# PCB_schematic_v1_0.net
KiCad netlist of a schematic drawn in EAGLE
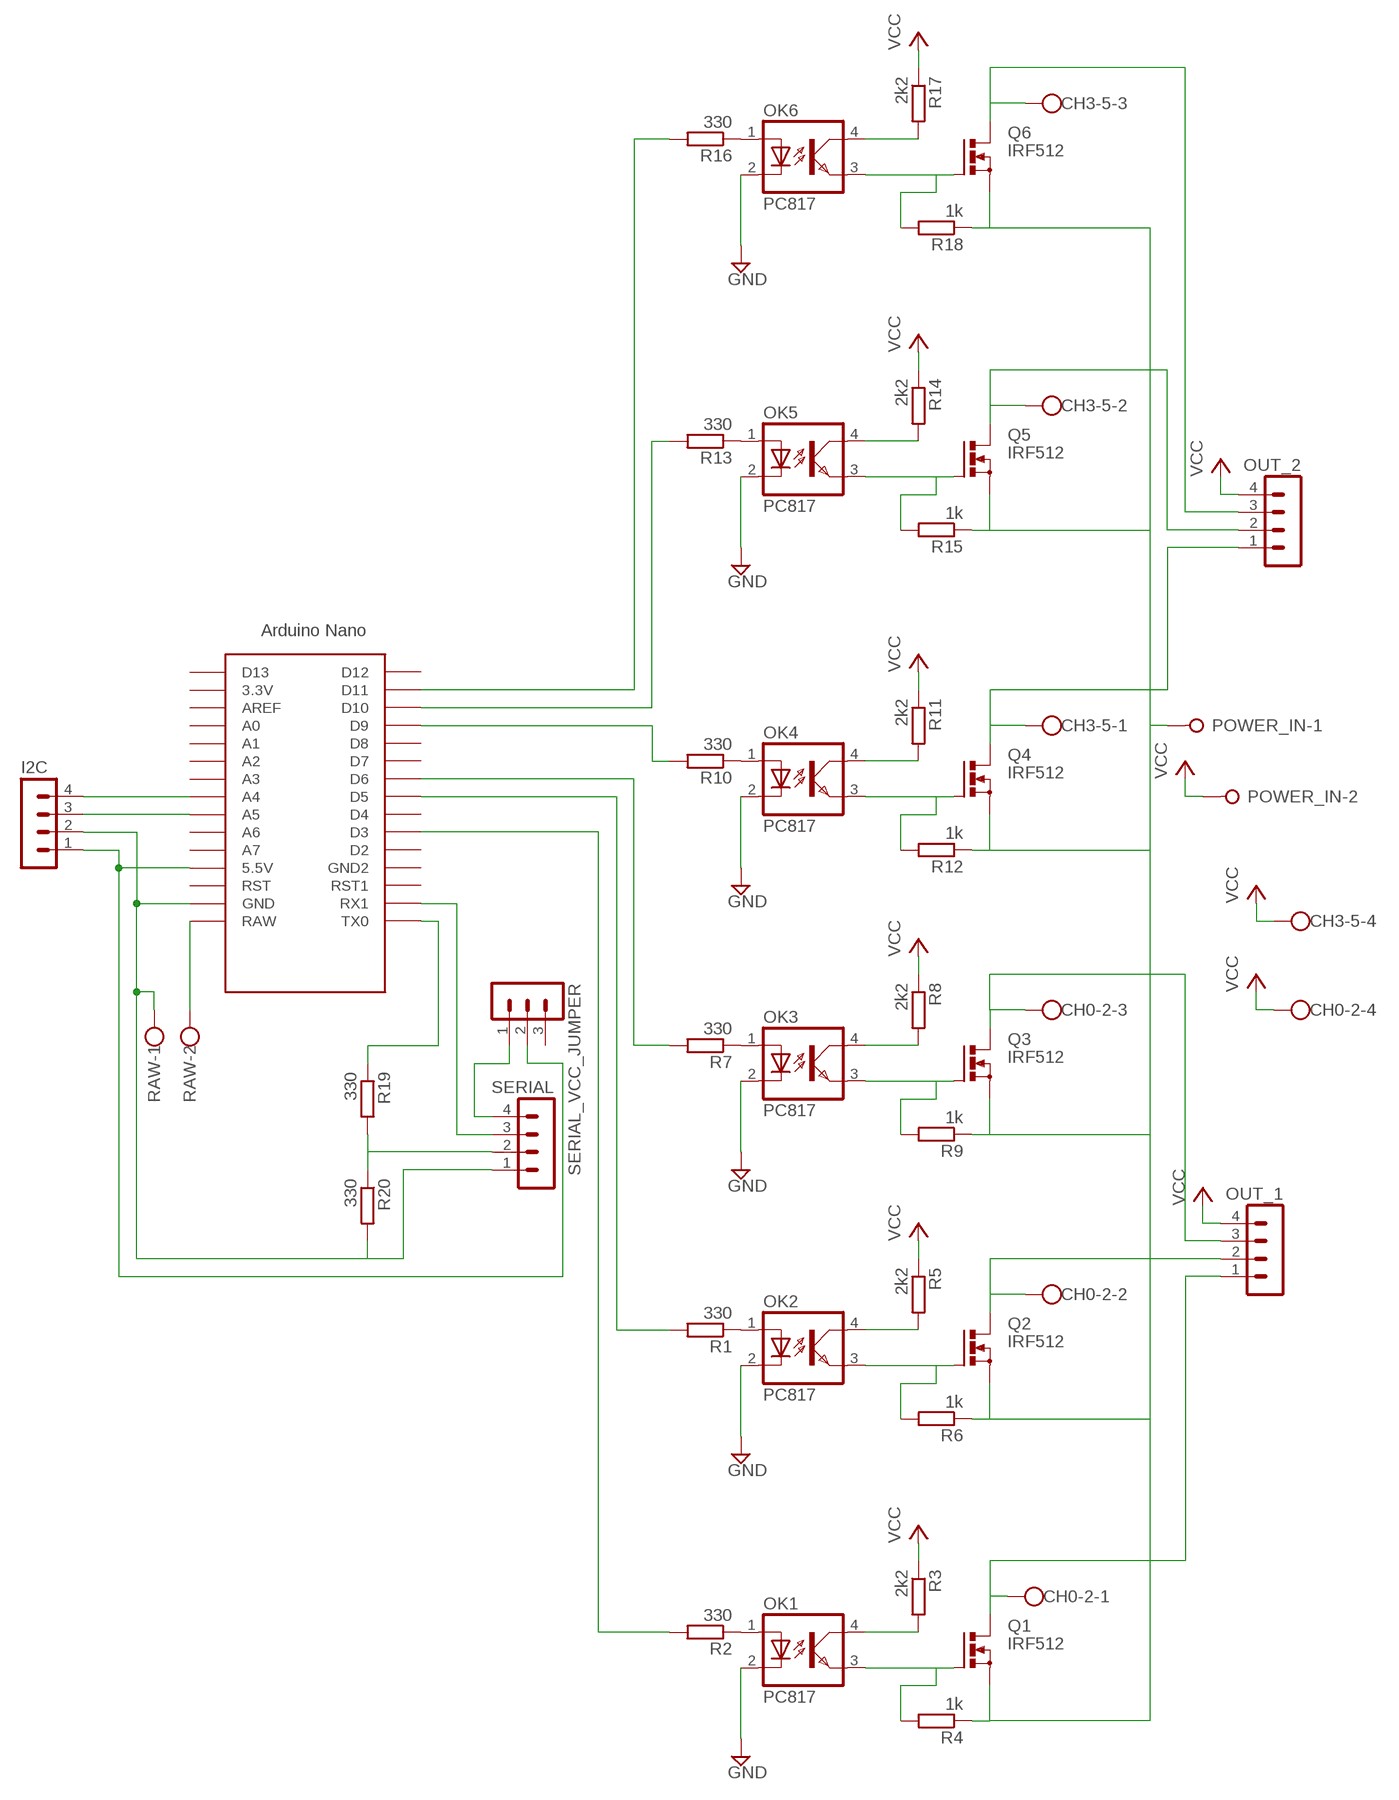
[diagram p0: schematic, sheet 1]

(export (version "E")
  (design (tool "Eeschema 10.0.6"))
  (components
    (comp (ref "CH0-2")
      (value "W237-4")
      (footprint "eagle-import:W237-4")
      (libsource (lib "eagle-import") (part "W237-4"))
    )
    (comp (ref "CH3-5")
      (value "W237-4")
      (footprint "eagle-import:W237-4")
      (libsource (lib "eagle-import") (part "W237-4"))
    )
    (comp (ref "I2C")
      (value "MA04-1")
      (footprint "eagle-import:MA04-1")
      (libsource (lib "eagle-import") (part "MA04-1"))
    )
    (comp (ref "OK1")
      (value "PC817")
      (footprint "eagle-import:DIL04")
      (fields (field (name "MPN") "PC817X4J000F"))
      (libsource (lib "eagle-import") (part "PC817"))
    )
    (comp (ref "OK2")
      (value "PC817")
      (footprint "eagle-import:DIL04")
      (fields (field (name "MPN") "PC817X4J000F"))
      (libsource (lib "eagle-import") (part "PC817"))
    )
    (comp (ref "OK3")
      (value "PC817")
      (footprint "eagle-import:DIL04")
      (fields (field (name "MPN") "PC817X4J000F"))
      (libsource (lib "eagle-import") (part "PC817"))
    )
    (comp (ref "OK4")
      (value "PC817")
      (footprint "eagle-import:DIL04")
      (fields (field (name "MPN") "PC817X4J000F"))
      (libsource (lib "eagle-import") (part "PC817"))
    )
    (comp (ref "OK5")
      (value "PC817")
      (footprint "eagle-import:DIL04")
      (fields (field (name "MPN") "PC817X4J000F"))
      (libsource (lib "eagle-import") (part "PC817"))
    )
    (comp (ref "OK6")
      (value "PC817")
      (footprint "eagle-import:DIL04")
      (fields (field (name "MPN") "PC817X4J000F"))
      (libsource (lib "eagle-import") (part "PC817"))
    )
    (comp (ref "OUT_1")
      (value "MA04-1")
      (footprint "eagle-import:MA04-1")
      (libsource (lib "eagle-import") (part "MA04-1"))
    )
    (comp (ref "OUT_2")
      (value "MA04-1")
      (footprint "eagle-import:MA04-1")
      (libsource (lib "eagle-import") (part "MA04-1"))
    )
    (comp (ref "POWER_IN")
      (value "W237-02P")
      (footprint "eagle-import:W237-132")
      (libsource (lib "eagle-import") (part "W237-02P"))
    )
    (comp (ref "Q1")
      (value "IRF512")
      (footprint "eagle-import:TO220BV")
      (libsource (lib "eagle-import") (part "IRF512"))
    )
    (comp (ref "Q2")
      (value "IRF512")
      (footprint "eagle-import:TO220BV")
      (libsource (lib "eagle-import") (part "IRF512"))
    )
    (comp (ref "Q3")
      (value "IRF512")
      (footprint "eagle-import:TO220BV")
      (libsource (lib "eagle-import") (part "IRF512"))
    )
    (comp (ref "Q4")
      (value "IRF512")
      (footprint "eagle-import:TO220BV")
      (libsource (lib "eagle-import") (part "IRF512"))
    )
    (comp (ref "Q5")
      (value "IRF512")
      (footprint "eagle-import:TO220BV")
      (libsource (lib "eagle-import") (part "IRF512"))
    )
    (comp (ref "Q6")
      (value "IRF512")
      (footprint "eagle-import:TO220BV")
      (libsource (lib "eagle-import") (part "IRF512"))
    )
    (comp (ref "R1")
      (value "330")
      (footprint "eagle-import:0207_10")
      (libsource (lib "eagle-import") (part "R-EU_0207/10"))
    )
    (comp (ref "R2")
      (value "330")
      (footprint "eagle-import:0207_10")
      (libsource (lib "eagle-import") (part "R-EU_0207/10"))
    )
    (comp (ref "R3")
      (value "2k2")
      (footprint "eagle-import:0207_10")
      (libsource (lib "eagle-import") (part "R-EU_0207/10"))
    )
    (comp (ref "R4")
      (value "1k")
      (footprint "eagle-import:0207_10")
      (libsource (lib "eagle-import") (part "R-EU_0207/10"))
    )
    (comp (ref "R5")
      (value "2k2")
      (footprint "eagle-import:0207_10")
      (libsource (lib "eagle-import") (part "R-EU_0207/10"))
    )
    (comp (ref "R6")
      (value "1k")
      (footprint "eagle-import:0207_10")
      (libsource (lib "eagle-import") (part "R-EU_0207/10"))
    )
    (comp (ref "R7")
      (value "330")
      (footprint "eagle-import:0207_10")
      (libsource (lib "eagle-import") (part "R-EU_0207/10"))
    )
    (comp (ref "R8")
      (value "2k2")
      (footprint "eagle-import:0207_10")
      (libsource (lib "eagle-import") (part "R-EU_0207/10"))
    )
    (comp (ref "R9")
      (value "1k")
      (footprint "eagle-import:0207_10")
      (libsource (lib "eagle-import") (part "R-EU_0207/10"))
    )
    (comp (ref "R10")
      (value "330")
      (footprint "eagle-import:0207_10")
      (libsource (lib "eagle-import") (part "R-EU_0207/10"))
    )
    (comp (ref "R11")
      (value "2k2")
      (footprint "eagle-import:0207_10")
      (libsource (lib "eagle-import") (part "R-EU_0207/10"))
    )
    (comp (ref "R12")
      (value "1k")
      (footprint "eagle-import:0207_10")
      (libsource (lib "eagle-import") (part "R-EU_0207/10"))
    )
    (comp (ref "R13")
      (value "330")
      (footprint "eagle-import:0207_10")
      (libsource (lib "eagle-import") (part "R-EU_0207/10"))
    )
    (comp (ref "R14")
      (value "2k2")
      (footprint "eagle-import:0207_10")
      (libsource (lib "eagle-import") (part "R-EU_0207/10"))
    )
    (comp (ref "R15")
      (value "1k")
      (footprint "eagle-import:0207_10")
      (libsource (lib "eagle-import") (part "R-EU_0207/10"))
    )
    (comp (ref "R16")
      (value "330")
      (footprint "eagle-import:0207_10")
      (libsource (lib "eagle-import") (part "R-EU_0207/10"))
    )
    (comp (ref "R17")
      (value "2k2")
      (footprint "eagle-import:0207_10")
      (libsource (lib "eagle-import") (part "R-EU_0207/10"))
    )
    (comp (ref "R18")
      (value "1k")
      (footprint "eagle-import:0207_10")
      (libsource (lib "eagle-import") (part "R-EU_0207/10"))
    )
    (comp (ref "R19")
      (value "330")
      (footprint "eagle-import:0207_10")
      (libsource (lib "eagle-import") (part "R-EU_0207/10"))
    )
    (comp (ref "R20")
      (value "330")
      (footprint "eagle-import:0207_10")
      (libsource (lib "eagle-import") (part "R-EU_0207/10"))
    )
    (comp (ref "RAW")
      (value "W237-102")
      (footprint "eagle-import:W237-102")
      (fields (field (name "MPN") "237-102"))
      (libsource (lib "eagle-import") (part "W237-102"))
    )
    (comp (ref "SERIAL")
      (value "MA04-1")
      (footprint "eagle-import:MA04-1")
      (libsource (lib "eagle-import") (part "MA04-1"))
    )
    (comp (ref "SERIAL_VCC_JUMPER")
      (value "MA03-1")
      (footprint "eagle-import:MA03-1")
      (libsource (lib "eagle-import") (part "MA03-1"))
    )
    (comp (ref "U$1")
      (value "NANO")
      (footprint "eagle-import:NANO")
      (libsource (lib "eagle-import") (part "NANO"))
    )
  )
  (nets
    (net (code "1") (name "GND") (class "Default")
      (node (ref "OK1") (pin "2") (pinfunction "C_2") (pintype "passive"))
      (node (ref "OK2") (pin "2") (pinfunction "C_2") (pintype "passive"))
      (node (ref "OK3") (pin "2") (pinfunction "C_2") (pintype "passive"))
      (node (ref "OK4") (pin "2") (pinfunction "C_2") (pintype "passive"))
      (node (ref "OK5") (pin "2") (pinfunction "C_2") (pintype "passive"))
      (node (ref "OK6") (pin "2") (pinfunction "C_2") (pintype "passive"))
    )
    (net (code "2") (name "Net-(CH0-2A-KL)") (class "Default")
      (node (ref "CH0-2") (pin "1") (pinfunction "KL_1") (pintype "passive"))
      (node (ref "OUT_1") (pin "1") (pinfunction "1_1") (pintype "passive"))
      (node (ref "Q1") (pin "D") (pinfunction "D_D") (pintype "passive"))
    )
    (net (code "3") (name "Net-(CH0-2B-KL)") (class "Default")
      (node (ref "CH0-2") (pin "2") (pinfunction "KL_2") (pintype "passive"))
      (node (ref "OUT_1") (pin "2") (pinfunction "2_2") (pintype "passive"))
      (node (ref "Q2") (pin "D") (pinfunction "D_D") (pintype "passive"))
    )
    (net (code "4") (name "Net-(CH0-2C-KL)") (class "Default")
      (node (ref "CH0-2") (pin "3") (pinfunction "KL_3") (pintype "passive"))
      (node (ref "OUT_1") (pin "3") (pinfunction "3_3") (pintype "passive"))
      (node (ref "Q3") (pin "D") (pinfunction "D_D") (pintype "passive"))
    )
    (net (code "5") (name "Net-(CH3-5A-KL)") (class "Default")
      (node (ref "CH3-5") (pin "1") (pinfunction "KL_1") (pintype "passive"))
      (node (ref "OUT_2") (pin "1") (pinfunction "1_1") (pintype "passive"))
      (node (ref "Q4") (pin "D") (pinfunction "D_D") (pintype "passive"))
    )
    (net (code "6") (name "Net-(CH3-5B-KL)") (class "Default")
      (node (ref "CH3-5") (pin "2") (pinfunction "KL_2") (pintype "passive"))
      (node (ref "OUT_2") (pin "2") (pinfunction "2_2") (pintype "passive"))
      (node (ref "Q5") (pin "D") (pinfunction "D_D") (pintype "passive"))
    )
    (net (code "7") (name "Net-(CH3-5C-KL)") (class "Default")
      (node (ref "CH3-5") (pin "3") (pinfunction "KL_3") (pintype "passive"))
      (node (ref "OUT_2") (pin "3") (pinfunction "3_3") (pintype "passive"))
      (node (ref "Q6") (pin "D") (pinfunction "D_D") (pintype "passive"))
    )
    (net (code "8") (name "Net-(I2C-Pad3)") (class "Default")
      (node (ref "I2C") (pin "3") (pinfunction "3_3") (pintype "passive"))
      (node (ref "U$1") (pin "A5") (pinfunction "A5_A5") (pintype "bidirectional"))
    )
    (net (code "9") (name "Net-(I2C-Pad4)") (class "Default")
      (node (ref "I2C") (pin "4") (pinfunction "4_4") (pintype "passive"))
      (node (ref "U$1") (pin "A4") (pinfunction "A4_A4") (pintype "bidirectional"))
    )
    (net (code "10") (name "Net-(OK1-A)") (class "Default")
      (node (ref "OK1") (pin "1") (pinfunction "A_1") (pintype "passive"))
      (node (ref "R2") (pin "1") (pinfunction "1_1") (pintype "passive"))
    )
    (net (code "11") (name "Net-(OK1-COL)") (class "Default")
      (node (ref "OK1") (pin "4") (pinfunction "COL_4") (pintype "passive"))
      (node (ref "R3") (pin "2") (pinfunction "2_2") (pintype "passive"))
    )
    (net (code "12") (name "Net-(OK1-EMIT)") (class "Default")
      (node (ref "OK1") (pin "3") (pinfunction "EMIT_3") (pintype "passive"))
      (node (ref "Q1") (pin "G") (pinfunction "G_G") (pintype "passive"))
      (node (ref "R4") (pin "2") (pinfunction "2_2") (pintype "passive"))
    )
    (net (code "13") (name "Net-(OK2-A)") (class "Default")
      (node (ref "OK2") (pin "1") (pinfunction "A_1") (pintype "passive"))
      (node (ref "R1") (pin "1") (pinfunction "1_1") (pintype "passive"))
    )
    (net (code "14") (name "Net-(OK2-COL)") (class "Default")
      (node (ref "OK2") (pin "4") (pinfunction "COL_4") (pintype "passive"))
      (node (ref "R5") (pin "2") (pinfunction "2_2") (pintype "passive"))
    )
    (net (code "15") (name "Net-(OK2-EMIT)") (class "Default")
      (node (ref "OK2") (pin "3") (pinfunction "EMIT_3") (pintype "passive"))
      (node (ref "Q2") (pin "G") (pinfunction "G_G") (pintype "passive"))
      (node (ref "R6") (pin "2") (pinfunction "2_2") (pintype "passive"))
    )
    (net (code "16") (name "Net-(OK3-A)") (class "Default")
      (node (ref "OK3") (pin "1") (pinfunction "A_1") (pintype "passive"))
      (node (ref "R7") (pin "1") (pinfunction "1_1") (pintype "passive"))
    )
    (net (code "17") (name "Net-(OK3-COL)") (class "Default")
      (node (ref "OK3") (pin "4") (pinfunction "COL_4") (pintype "passive"))
      (node (ref "R8") (pin "2") (pinfunction "2_2") (pintype "passive"))
    )
    (net (code "18") (name "Net-(OK3-EMIT)") (class "Default")
      (node (ref "OK3") (pin "3") (pinfunction "EMIT_3") (pintype "passive"))
      (node (ref "Q3") (pin "G") (pinfunction "G_G") (pintype "passive"))
      (node (ref "R9") (pin "2") (pinfunction "2_2") (pintype "passive"))
    )
    (net (code "19") (name "Net-(OK4-A)") (class "Default")
      (node (ref "OK4") (pin "1") (pinfunction "A_1") (pintype "passive"))
      (node (ref "R10") (pin "1") (pinfunction "1_1") (pintype "passive"))
    )
    (net (code "20") (name "Net-(OK4-COL)") (class "Default")
      (node (ref "OK4") (pin "4") (pinfunction "COL_4") (pintype "passive"))
      (node (ref "R11") (pin "2") (pinfunction "2_2") (pintype "passive"))
    )
    (net (code "21") (name "Net-(OK4-EMIT)") (class "Default")
      (node (ref "OK4") (pin "3") (pinfunction "EMIT_3") (pintype "passive"))
      (node (ref "Q4") (pin "G") (pinfunction "G_G") (pintype "passive"))
      (node (ref "R12") (pin "2") (pinfunction "2_2") (pintype "passive"))
    )
    (net (code "22") (name "Net-(OK5-A)") (class "Default")
      (node (ref "OK5") (pin "1") (pinfunction "A_1") (pintype "passive"))
      (node (ref "R13") (pin "1") (pinfunction "1_1") (pintype "passive"))
    )
    (net (code "23") (name "Net-(OK5-COL)") (class "Default")
      (node (ref "OK5") (pin "4") (pinfunction "COL_4") (pintype "passive"))
      (node (ref "R14") (pin "2") (pinfunction "2_2") (pintype "passive"))
    )
    (net (code "24") (name "Net-(OK5-EMIT)") (class "Default")
      (node (ref "OK5") (pin "3") (pinfunction "EMIT_3") (pintype "passive"))
      (node (ref "Q5") (pin "G") (pinfunction "G_G") (pintype "passive"))
      (node (ref "R15") (pin "2") (pinfunction "2_2") (pintype "passive"))
    )
    (net (code "25") (name "Net-(OK6-A)") (class "Default")
      (node (ref "OK6") (pin "1") (pinfunction "A_1") (pintype "passive"))
      (node (ref "R16") (pin "1") (pinfunction "1_1") (pintype "passive"))
    )
    (net (code "26") (name "Net-(OK6-COL)") (class "Default")
      (node (ref "OK6") (pin "4") (pinfunction "COL_4") (pintype "passive"))
      (node (ref "R17") (pin "2") (pinfunction "2_2") (pintype "passive"))
    )
    (net (code "27") (name "Net-(OK6-EMIT)") (class "Default")
      (node (ref "OK6") (pin "3") (pinfunction "EMIT_3") (pintype "passive"))
      (node (ref "Q6") (pin "G") (pinfunction "G_G") (pintype "passive"))
      (node (ref "R18") (pin "2") (pinfunction "2_2") (pintype "passive"))
    )
    (net (code "28") (name "Net-(POWER_INA-KL)") (class "Default")
      (node (ref "POWER_IN") (pin "1") (pinfunction "KL_1") (pintype "passive"))
      (node (ref "Q1") (pin "S") (pinfunction "S_S") (pintype "passive"))
      (node (ref "Q2") (pin "S") (pinfunction "S_S") (pintype "passive"))
      (node (ref "Q3") (pin "S") (pinfunction "S_S") (pintype "passive"))
      (node (ref "Q4") (pin "S") (pinfunction "S_S") (pintype "passive"))
      (node (ref "Q5") (pin "S") (pinfunction "S_S") (pintype "passive"))
      (node (ref "Q6") (pin "S") (pinfunction "S_S") (pintype "passive"))
      (node (ref "R12") (pin "1") (pinfunction "1_1") (pintype "passive"))
      (node (ref "R15") (pin "1") (pinfunction "1_1") (pintype "passive"))
      (node (ref "R18") (pin "1") (pinfunction "1_1") (pintype "passive"))
      (node (ref "R4") (pin "1") (pinfunction "1_1") (pintype "passive"))
      (node (ref "R6") (pin "1") (pinfunction "1_1") (pintype "passive"))
      (node (ref "R9") (pin "1") (pinfunction "1_1") (pintype "passive"))
    )
    (net (code "29") (name "Net-(R1-Pad2)") (class "Default")
      (node (ref "R1") (pin "2") (pinfunction "2_2") (pintype "passive"))
      (node (ref "U$1") (pin "D5") (pinfunction "D5_D5") (pintype "bidirectional"))
    )
    (net (code "30") (name "Net-(R2-Pad2)") (class "Default")
      (node (ref "R2") (pin "2") (pinfunction "2_2") (pintype "passive"))
      (node (ref "U$1") (pin "D3") (pinfunction "D3_D3") (pintype "bidirectional"))
    )
    (net (code "31") (name "Net-(R7-Pad2)") (class "Default")
      (node (ref "R7") (pin "2") (pinfunction "2_2") (pintype "passive"))
      (node (ref "U$1") (pin "D6") (pinfunction "D6_D6") (pintype "bidirectional"))
    )
    (net (code "32") (name "Net-(R10-Pad2)") (class "Default")
      (node (ref "R10") (pin "2") (pinfunction "2_2") (pintype "passive"))
      (node (ref "U$1") (pin "D9") (pinfunction "D9_D9") (pintype "bidirectional"))
    )
    (net (code "33") (name "Net-(R13-Pad2)") (class "Default")
      (node (ref "R13") (pin "2") (pinfunction "2_2") (pintype "passive"))
      (node (ref "U$1") (pin "D10") (pinfunction "D10_D10") (pintype "bidirectional"))
    )
    (net (code "34") (name "Net-(R16-Pad2)") (class "Default")
      (node (ref "R16") (pin "2") (pinfunction "2_2") (pintype "passive"))
      (node (ref "U$1") (pin "D11") (pinfunction "D11_D11") (pintype "bidirectional"))
    )
    (net (code "35") (name "Net-(R19-Pad1)") (class "Default")
      (node (ref "R19") (pin "1") (pinfunction "1_1") (pintype "passive"))
      (node (ref "U$1") (pin "TX0") (pinfunction "TX0_TX0") (pintype "bidirectional"))
    )
    (net (code "36") (name "Net-(R19-Pad2)") (class "Default")
      (node (ref "R19") (pin "2") (pinfunction "2_2") (pintype "passive"))
      (node (ref "R20") (pin "1") (pinfunction "1_1") (pintype "passive"))
      (node (ref "SERIAL") (pin "2") (pinfunction "2_2") (pintype "passive"))
    )
    (net (code "37") (name "Net-(RAWA-KL)") (class "Default")
      (node (ref "I2C") (pin "2") (pinfunction "2_2") (pintype "passive"))
      (node (ref "R20") (pin "2") (pinfunction "2_2") (pintype "passive"))
      (node (ref "RAW") (pin "1") (pinfunction "KL_1") (pintype "passive"))
      (node (ref "SERIAL") (pin "1") (pinfunction "1_1") (pintype "passive"))
      (node (ref "U$1") (pin "GND") (pinfunction "GND_GND") (pintype "bidirectional"))
    )
    (net (code "38") (name "Net-(RAWB-KL)") (class "Default")
      (node (ref "RAW") (pin "2") (pinfunction "KL_2") (pintype "passive"))
      (node (ref "U$1") (pin "RAW") (pinfunction "RAW_RAW") (pintype "bidirectional"))
    )
    (net (code "39") (name "Net-(SERIAL-Pad3)") (class "Default")
      (node (ref "SERIAL") (pin "3") (pinfunction "3_3") (pintype "passive"))
      (node (ref "U$1") (pin "RX1") (pinfunction "RX1_RX1") (pintype "bidirectional"))
    )
    (net (code "40") (name "Net-(SERIAL-Pad4)") (class "Default")
      (node (ref "SERIAL") (pin "4") (pinfunction "4_4") (pintype "passive"))
      (node (ref "SERIAL_VCC_JUMPER") (pin "1") (pinfunction "1_1") (pintype "passive"))
    )
    (net (code "41") (name "Net-(U$1-5.5V)") (class "Default")
      (node (ref "I2C") (pin "1") (pinfunction "1_1") (pintype "passive"))
      (node (ref "SERIAL_VCC_JUMPER") (pin "2") (pinfunction "2_2") (pintype "passive"))
      (node (ref "U$1") (pin "5V") (pinfunction "5.5V_5V") (pintype "bidirectional"))
    )
    (net (code "42") (name "VCC") (class "Default")
      (node (ref "CH0-2") (pin "4") (pinfunction "KL_4") (pintype "passive"))
      (node (ref "CH3-5") (pin "4") (pinfunction "KL_4") (pintype "passive"))
      (node (ref "OUT_1") (pin "4") (pinfunction "4_4") (pintype "passive"))
      (node (ref "OUT_2") (pin "4") (pinfunction "4_4") (pintype "passive"))
      (node (ref "POWER_IN") (pin "2") (pinfunction "KL_2") (pintype "passive"))
      (node (ref "R11") (pin "1") (pinfunction "1_1") (pintype "passive"))
      (node (ref "R14") (pin "1") (pinfunction "1_1") (pintype "passive"))
      (node (ref "R17") (pin "1") (pinfunction "1_1") (pintype "passive"))
      (node (ref "R3") (pin "1") (pinfunction "1_1") (pintype "passive"))
      (node (ref "R5") (pin "1") (pinfunction "1_1") (pintype "passive"))
      (node (ref "R8") (pin "1") (pinfunction "1_1") (pintype "passive"))
    )
    (net (code "43") (name "unconnected-(SERIAL_VCC_JUMPER-Pad3)") (class "Default")
      (node (ref "SERIAL_VCC_JUMPER") (pin "3") (pinfunction "3_3") (pintype "passive"))
    )
    (net (code "44") (name "unconnected-(U$1-GND2-PadGND1)") (class "Default")
      (node (ref "U$1") (pin "GND1") (pinfunction "GND2_GND1") (pintype "bidirectional"))
    )
    (net (code "45") (name "unconnected-(U$1-Pad3.3V)") (class "Default")
      (node (ref "U$1") (pin "3.3V") (pinfunction "3.3V_3.3V") (pintype "bidirectional"))
    )
    (net (code "46") (name "unconnected-(U$1-PadA0)") (class "Default")
      (node (ref "U$1") (pin "A0") (pinfunction "A0_A0") (pintype "bidirectional"))
    )
    (net (code "47") (name "unconnected-(U$1-PadA1)") (class "Default")
      (node (ref "U$1") (pin "A1") (pinfunction "A1_A1") (pintype "bidirectional"))
    )
    (net (code "48") (name "unconnected-(U$1-PadA2)") (class "Default")
      (node (ref "U$1") (pin "A2") (pinfunction "A2_A2") (pintype "bidirectional"))
    )
    (net (code "49") (name "unconnected-(U$1-PadA3)") (class "Default")
      (node (ref "U$1") (pin "A3") (pinfunction "A3_A3") (pintype "bidirectional"))
    )
    (net (code "50") (name "unconnected-(U$1-PadA6)") (class "Default")
      (node (ref "U$1") (pin "A6") (pinfunction "A6_A6") (pintype "bidirectional"))
    )
    (net (code "51") (name "unconnected-(U$1-PadA7)") (class "Default")
      (node (ref "U$1") (pin "A7") (pinfunction "A7_A7") (pintype "bidirectional"))
    )
    (net (code "52") (name "unconnected-(U$1-PadAREF)") (class "Default")
      (node (ref "U$1") (pin "AREF") (pinfunction "AREF_AREF") (pintype "bidirectional"))
    )
    (net (code "53") (name "unconnected-(U$1-PadD2)") (class "Default")
      (node (ref "U$1") (pin "D2") (pinfunction "D2_D2") (pintype "bidirectional"))
    )
    (net (code "54") (name "unconnected-(U$1-PadD4)") (class "Default")
      (node (ref "U$1") (pin "D4") (pinfunction "D4_D4") (pintype "bidirectional"))
    )
    (net (code "55") (name "unconnected-(U$1-PadD7)") (class "Default")
      (node (ref "U$1") (pin "D7") (pinfunction "D7_D7") (pintype "bidirectional"))
    )
    (net (code "56") (name "unconnected-(U$1-PadD8)") (class "Default")
      (node (ref "U$1") (pin "D8") (pinfunction "D8_D8") (pintype "bidirectional"))
    )
    (net (code "57") (name "unconnected-(U$1-PadD12)") (class "Default")
      (node (ref "U$1") (pin "D12") (pinfunction "D12_D12") (pintype "bidirectional"))
    )
    (net (code "58") (name "unconnected-(U$1-PadD13)") (class "Default")
      (node (ref "U$1") (pin "D13") (pinfunction "D13_D13") (pintype "bidirectional"))
    )
    (net (code "59") (name "unconnected-(U$1-PadICSP1)") (class "Default")
      (node (ref "U$1") (pin "ICSP1") (pinfunction "ICSP1_ICSP1") (pintype "bidirectional"))
    )
    (net (code "60") (name "unconnected-(U$1-PadICSP2)") (class "Default")
      (node (ref "U$1") (pin "ICSP2") (pinfunction "ICSP2_ICSP2") (pintype "bidirectional"))
    )
    (net (code "61") (name "unconnected-(U$1-PadICSP3)") (class "Default")
      (node (ref "U$1") (pin "ICSP3") (pinfunction "ICSP3_ICSP3") (pintype "bidirectional"))
    )
    (net (code "62") (name "unconnected-(U$1-PadICSP4)") (class "Default")
      (node (ref "U$1") (pin "ICSP4") (pinfunction "ICSP4_ICSP4") (pintype "bidirectional"))
    )
    (net (code "63") (name "unconnected-(U$1-PadICSP5)") (class "Default")
      (node (ref "U$1") (pin "ICSP5") (pinfunction "ICSP5_ICSP5") (pintype "bidirectional"))
    )
    (net (code "64") (name "unconnected-(U$1-PadICSP6)") (class "Default")
      (node (ref "U$1") (pin "ICSP6") (pinfunction "ICSP6_ICSP6") (pintype "bidirectional"))
    )
    (net (code "65") (name "unconnected-(U$1-PadRST)") (class "Default")
      (node (ref "U$1") (pin "RST") (pinfunction "RST_RST") (pintype "bidirectional"))
    )
    (net (code "66") (name "unconnected-(U$1-PadRST1)") (class "Default")
      (node (ref "U$1") (pin "RST1") (pinfunction "RST1_RST1") (pintype "bidirectional"))
    )
  )
)
